# basic-inline-turbidimeter_main_board_v2_.net
KiCad netlist of a schematic drawn in EAGLE
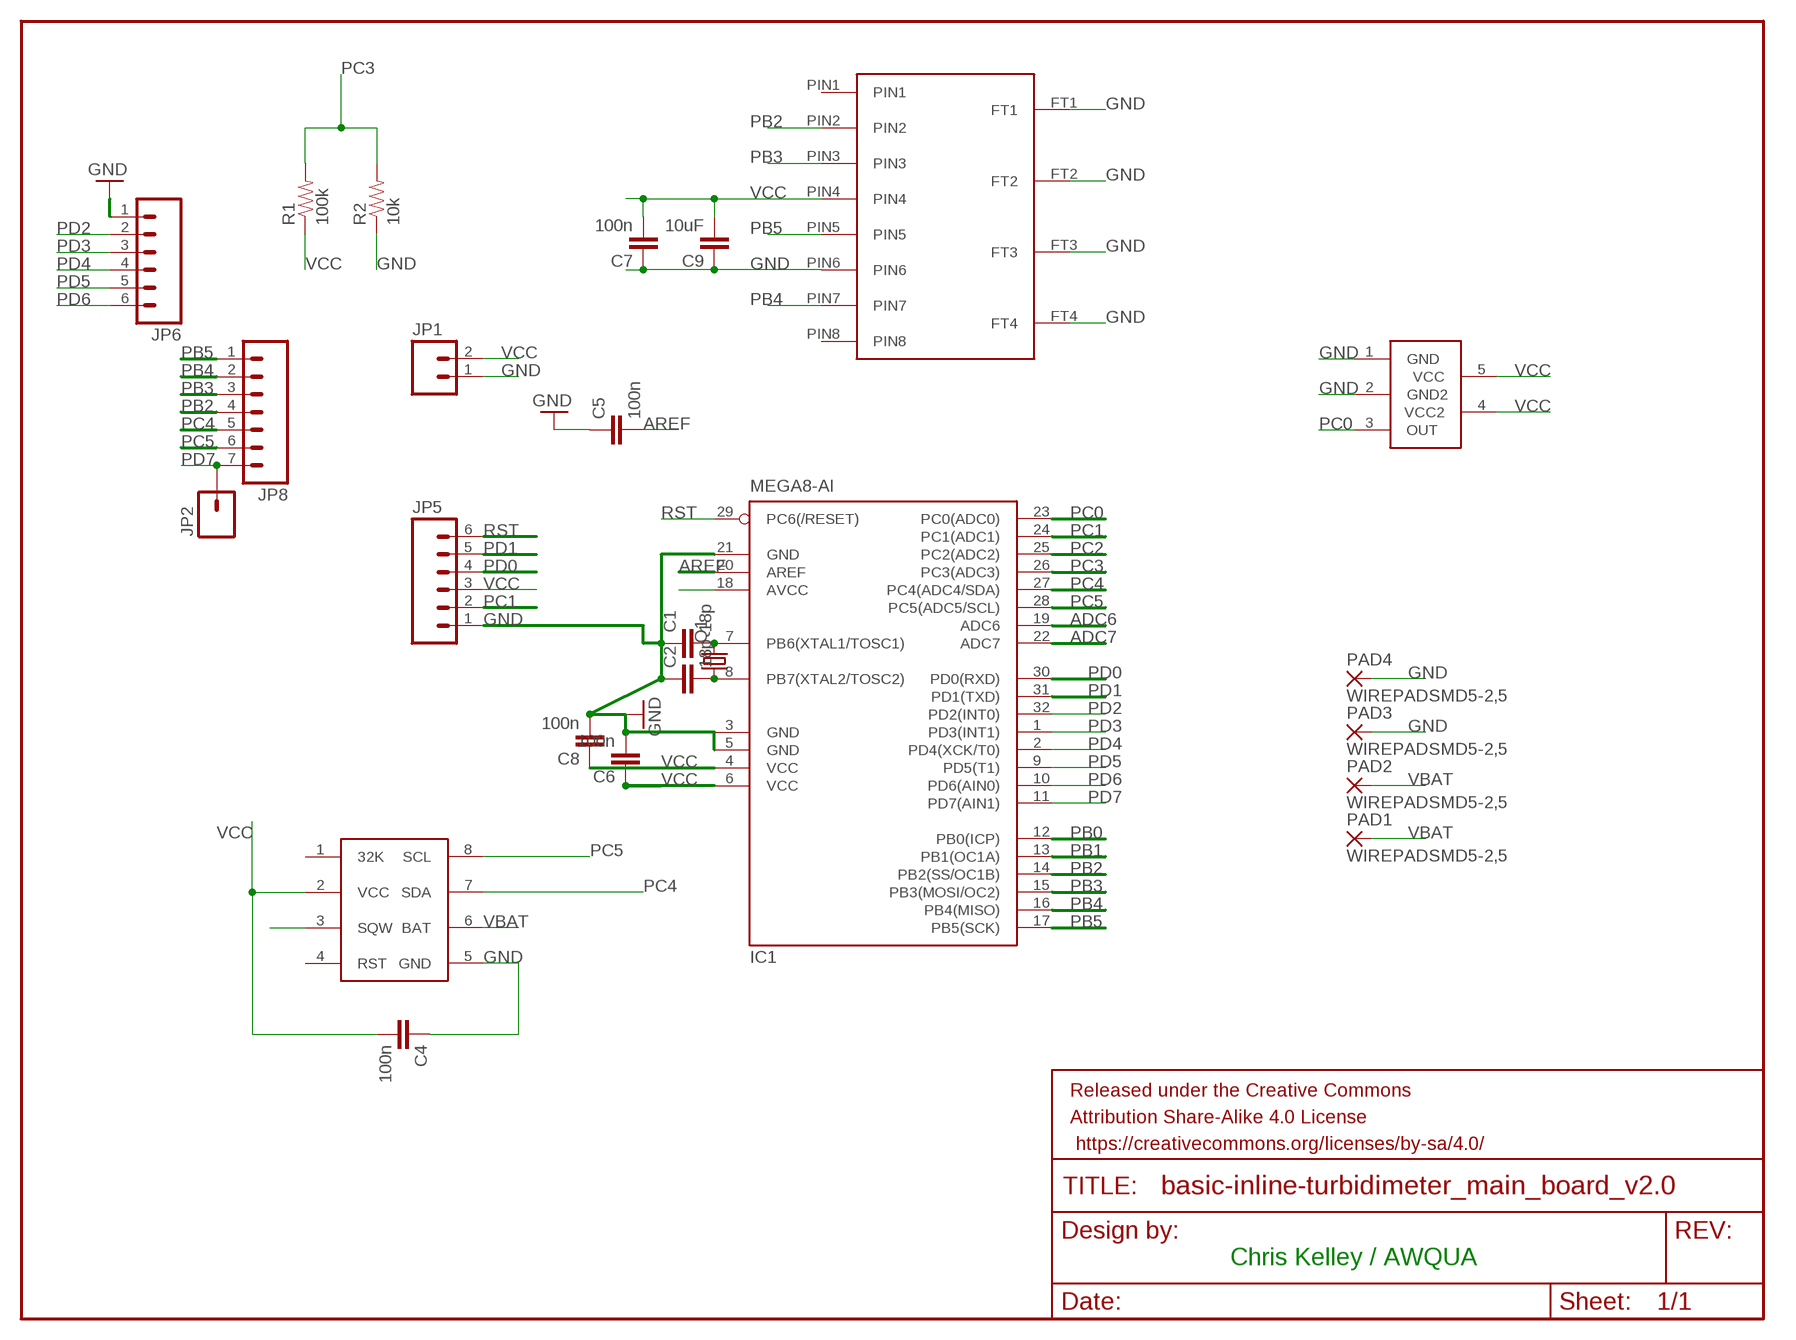
[diagram p0: schematic, sheet 1]

(export (version "E")
  (design (tool "Eeschema 10.0.6"))
  (components
    (comp (ref "*RTC")
      (value "DS3231M")
      (footprint "eagle-import:DS3231M")
      (libsource (lib "eagle-import") (part "DS3231M"))
    )
    (comp (ref "C1")
      (value "18p")
      (footprint "eagle-import:0603-CAP")
      (libsource (lib "eagle-import") (part "CAP0603-CAP"))
    )
    (comp (ref "C2")
      (value "18p")
      (footprint "eagle-import:0603-CAP")
      (libsource (lib "eagle-import") (part "CAP0603-CAP"))
    )
    (comp (ref "C4")
      (value "100n")
      (footprint "eagle-import:0603-CAP")
      (libsource (lib "eagle-import") (part "CAP0603-CAP"))
    )
    (comp (ref "C5")
      (value "100n")
      (footprint "eagle-import:0603-CAP")
      (libsource (lib "eagle-import") (part "CAP0603-CAP"))
    )
    (comp (ref "C6")
      (value "100n")
      (footprint "eagle-import:0603-CAP")
      (libsource (lib "eagle-import") (part "CAP0603-CAP"))
    )
    (comp (ref "C7")
      (value "100n")
      (footprint "eagle-import:0603-CAP")
      (libsource (lib "eagle-import") (part "CAP0603-CAP"))
    )
    (comp (ref "C8")
      (value "100n")
      (footprint "eagle-import:0603-CAP")
      (libsource (lib "eagle-import") (part "CAP0603-CAP"))
    )
    (comp (ref "C9")
      (value "10uF")
      (footprint "eagle-import:0603-CAP")
      (libsource (lib "eagle-import") (part "CAP0603-CAP"))
    )
    (comp (ref "FRAME1")
      (value "FRAME-LETTER")
      (footprint "eagle-import:CREATIVE_COMMONS")
      (libsource (lib "eagle-import") (part "FRAME-LETTER"))
    )
    (comp (ref "IC1")
      (value "MEGA8-AI")
      (footprint "eagle-import:TQFP32-08")
      (fields (field (name "MPN") "ATMEGA8-16AU"))
      (libsource (lib "eagle-import") (part "MEGA8-AI"))
    )
    (comp (ref "JP1")
      (value "M02PTH")
      (footprint "eagle-import:1X02")
      (libsource (lib "eagle-import") (part "M02PTH"))
    )
    (comp (ref "JP2")
      (value "M01PTH")
      (footprint "eagle-import:1X01")
      (libsource (lib "eagle-import") (part "M01PTH"))
    )
    (comp (ref "JP5")
      (value "M06SILK_FEMALE_PTH")
      (footprint "eagle-import:1X06")
      (libsource (lib "eagle-import") (part "M06SILK_FEMALE_PTH"))
    )
    (comp (ref "JP6")
      (value "M06SILK_FEMALE_PTH")
      (footprint "eagle-import:1X06")
      (libsource (lib "eagle-import") (part "M06SILK_FEMALE_PTH"))
    )
    (comp (ref "JP8")
      (value "M07")
      (footprint "eagle-import:1X07")
      (libsource (lib "eagle-import") (part "M07"))
    )
    (comp (ref "MICRO-SD")
      (value "MICROSD-1010030368")
      (footprint "eagle-import:MICROSD-1010030368")
      (libsource (lib "eagle-import") (part "MICROSD-1010030368"))
    )
    (comp (ref "PAD1")
      (value "WIREPADSMD5-2,5")
      (footprint "eagle-import:5-2,5")
      (libsource (lib "eagle-import") (part "WIREPADSMD5-2,5"))
    )
    (comp (ref "PAD2")
      (value "WIREPADSMD5-2,5")
      (footprint "eagle-import:5-2,5")
      (libsource (lib "eagle-import") (part "WIREPADSMD5-2,5"))
    )
    (comp (ref "PAD3")
      (value "WIREPADSMD5-2,5")
      (footprint "eagle-import:5-2,5")
      (libsource (lib "eagle-import") (part "WIREPADSMD5-2,5"))
    )
    (comp (ref "PAD4")
      (value "WIREPADSMD5-2,5")
      (footprint "eagle-import:5-2,5")
      (libsource (lib "eagle-import") (part "WIREPADSMD5-2,5"))
    )
    (comp (ref "Q1")
      (value "CRYSTAL5X3")
      (footprint "eagle-import:CRYSTAL-SMD-5X3")
      (libsource (lib "eagle-import") (part "CRYSTAL5X3"))
    )
    (comp (ref "R1")
      (value "100k")
      (footprint "eagle-import:0603-RES")
      (libsource (lib "eagle-import") (part "RESISTOR0603"))
    )
    (comp (ref "R2")
      (value "10k")
      (footprint "eagle-import:0603-RES")
      (libsource (lib "eagle-import") (part "RESISTOR0603"))
    )
    (comp (ref "T1")
      (value "LMT86")
      (footprint "eagle-import:LMT86")
      (libsource (lib "eagle-import") (part "LMT86"))
    )
  )
  (nets
    (net (code "1") (name "/ADC6") (class "Default")
      (node (ref "IC1") (pin "19") (pinfunction "ADC6_19") (pintype "bidirectional"))
    )
    (net (code "2") (name "/ADC7") (class "Default")
      (node (ref "IC1") (pin "22") (pinfunction "ADC7_22") (pintype "bidirectional"))
    )
    (net (code "3") (name "/AREF") (class "Default")
      (node (ref "C5") (pin "2") (pinfunction "2_2") (pintype "passive"))
      (node (ref "IC1") (pin "20") (pinfunction "AREF_20") (pintype "passive"))
    )
    (net (code "4") (name "/PB0") (class "Default")
      (node (ref "IC1") (pin "12") (pinfunction "PB0(ICP)_12") (pintype "bidirectional"))
    )
    (net (code "5") (name "/PB1") (class "Default")
      (node (ref "IC1") (pin "13") (pinfunction "PB1(OC1A)_13") (pintype "bidirectional"))
    )
    (net (code "6") (name "/PB2") (class "Default")
      (node (ref "IC1") (pin "14") (pinfunction "PB2(SS/OC1B)_14") (pintype "bidirectional"))
      (node (ref "JP8") (pin "4") (pinfunction "4_4") (pintype "passive"))
      (node (ref "MICRO-SD") (pin "PIN2") (pinfunction "PIN2_PIN2") (pintype "bidirectional"))
    )
    (net (code "7") (name "/PB3") (class "Default")
      (node (ref "IC1") (pin "15") (pinfunction "PB3(MOSI/OC2)_15") (pintype "bidirectional"))
      (node (ref "JP8") (pin "3") (pinfunction "3_3") (pintype "passive"))
      (node (ref "MICRO-SD") (pin "PIN3") (pinfunction "PIN3_PIN3") (pintype "bidirectional"))
    )
    (net (code "8") (name "/PB4") (class "Default")
      (node (ref "IC1") (pin "16") (pinfunction "PB4(MISO)_16") (pintype "bidirectional"))
      (node (ref "JP8") (pin "2") (pinfunction "2_2") (pintype "passive"))
      (node (ref "MICRO-SD") (pin "PIN7") (pinfunction "PIN7_PIN7") (pintype "bidirectional"))
    )
    (net (code "9") (name "/PB5") (class "Default")
      (node (ref "IC1") (pin "17") (pinfunction "PB5(SCK)_17") (pintype "bidirectional"))
      (node (ref "JP8") (pin "1") (pinfunction "1_1") (pintype "passive"))
      (node (ref "MICRO-SD") (pin "PIN5") (pinfunction "PIN5_PIN5") (pintype "bidirectional"))
    )
    (net (code "10") (name "/PC0") (class "Default")
      (node (ref "IC1") (pin "23") (pinfunction "PC0(ADC0)_23") (pintype "bidirectional"))
      (node (ref "T1") (pin "3") (pinfunction "OUT_3") (pintype "bidirectional"))
    )
    (net (code "11") (name "/PC1") (class "Default")
      (node (ref "IC1") (pin "24") (pinfunction "PC1(ADC1)_24") (pintype "bidirectional"))
      (node (ref "JP5") (pin "2") (pinfunction "2_2") (pintype "passive"))
    )
    (net (code "12") (name "/PC2") (class "Default")
      (node (ref "IC1") (pin "25") (pinfunction "PC2(ADC2)_25") (pintype "bidirectional"))
    )
    (net (code "13") (name "/PC3") (class "Default")
      (node (ref "IC1") (pin "26") (pinfunction "PC3(ADC3)_26") (pintype "bidirectional"))
      (node (ref "R1") (pin "2") (pinfunction "2_2") (pintype "passive"))
      (node (ref "R2") (pin "2") (pinfunction "2_2") (pintype "passive"))
    )
    (net (code "14") (name "/PC4") (class "Default")
      (node (ref "*RTC") (pin "7") (pinfunction "SDA_7") (pintype "bidirectional"))
      (node (ref "IC1") (pin "27") (pinfunction "PC4(ADC4/SDA)_27") (pintype "bidirectional"))
      (node (ref "JP8") (pin "5") (pinfunction "5_5") (pintype "passive"))
    )
    (net (code "15") (name "/PC5") (class "Default")
      (node (ref "*RTC") (pin "8") (pinfunction "SCL_8") (pintype "bidirectional"))
      (node (ref "IC1") (pin "28") (pinfunction "PC5(ADC5/SCL)_28") (pintype "bidirectional"))
      (node (ref "JP8") (pin "6") (pinfunction "6_6") (pintype "passive"))
    )
    (net (code "16") (name "/PD0") (class "Default")
      (node (ref "IC1") (pin "30") (pinfunction "PD0(RXD)_30") (pintype "bidirectional"))
      (node (ref "JP5") (pin "4") (pinfunction "4_4") (pintype "passive"))
    )
    (net (code "17") (name "/PD1") (class "Default")
      (node (ref "IC1") (pin "31") (pinfunction "PD1(TXD)_31") (pintype "bidirectional"))
      (node (ref "JP5") (pin "5") (pinfunction "5_5") (pintype "passive"))
    )
    (net (code "18") (name "/PD2") (class "Default")
      (node (ref "IC1") (pin "32") (pinfunction "PD2(INT0)_32") (pintype "bidirectional"))
      (node (ref "JP6") (pin "2") (pinfunction "2_2") (pintype "passive"))
    )
    (net (code "19") (name "/PD3") (class "Default")
      (node (ref "IC1") (pin "1") (pinfunction "PD3(INT1)_1") (pintype "bidirectional"))
      (node (ref "JP6") (pin "3") (pinfunction "3_3") (pintype "passive"))
    )
    (net (code "20") (name "/PD4") (class "Default")
      (node (ref "IC1") (pin "2") (pinfunction "PD4(XCK/T0)_2") (pintype "bidirectional"))
      (node (ref "JP6") (pin "4") (pinfunction "4_4") (pintype "passive"))
    )
    (net (code "21") (name "/PD5") (class "Default")
      (node (ref "IC1") (pin "9") (pinfunction "PD5(T1)_9") (pintype "bidirectional"))
      (node (ref "JP6") (pin "5") (pinfunction "5_5") (pintype "passive"))
    )
    (net (code "22") (name "/PD6") (class "Default")
      (node (ref "IC1") (pin "10") (pinfunction "PD6(AIN0)_10") (pintype "bidirectional"))
      (node (ref "JP6") (pin "6") (pinfunction "6_6") (pintype "passive"))
    )
    (net (code "23") (name "/PD7") (class "Default")
      (node (ref "IC1") (pin "11") (pinfunction "PD7(AIN1)_11") (pintype "bidirectional"))
      (node (ref "JP2") (pin "1") (pinfunction "1_1") (pintype "passive"))
      (node (ref "JP8") (pin "7") (pinfunction "7_7") (pintype "passive"))
    )
    (net (code "24") (name "/RST") (class "Default")
      (node (ref "IC1") (pin "29") (pinfunction "PC6(/RESET)_29") (pintype "bidirectional"))
      (node (ref "JP5") (pin "6") (pinfunction "6_6") (pintype "passive"))
    )
    (net (code "25") (name "/VBAT") (class "Default")
      (node (ref "*RTC") (pin "6") (pinfunction "BAT_6") (pintype "bidirectional"))
      (node (ref "PAD1") (pin "1") (pinfunction "P_1") (pintype "passive"))
      (node (ref "PAD2") (pin "1") (pinfunction "P_1") (pintype "passive"))
    )
    (net (code "26") (name "/VCC") (class "Default")
      (node (ref "*RTC") (pin "2") (pinfunction "VCC_2") (pintype "bidirectional"))
      (node (ref "C4") (pin "2") (pinfunction "2_2") (pintype "passive"))
      (node (ref "C6") (pin "1") (pinfunction "1_1") (pintype "passive"))
      (node (ref "C7") (pin "2") (pinfunction "2_2") (pintype "passive"))
      (node (ref "C8") (pin "1") (pinfunction "1_1") (pintype "passive"))
      (node (ref "C9") (pin "2") (pinfunction "2_2") (pintype "passive"))
      (node (ref "IC1") (pin "18") (pinfunction "AVCC_18") (pintype "power_in"))
      (node (ref "IC1") (pin "4") (pinfunction "VCC_4") (pintype "power_in"))
      (node (ref "IC1") (pin "6") (pinfunction "VCC_6") (pintype "power_in"))
      (node (ref "JP1") (pin "2") (pinfunction "2_2") (pintype "passive"))
      (node (ref "JP5") (pin "3") (pinfunction "3_3") (pintype "passive"))
      (node (ref "MICRO-SD") (pin "PIN4") (pinfunction "PIN4_PIN4") (pintype "bidirectional"))
      (node (ref "R1") (pin "1") (pinfunction "1_1") (pintype "passive"))
      (node (ref "T1") (pin "4") (pinfunction "VCC2_4") (pintype "bidirectional"))
      (node (ref "T1") (pin "5") (pinfunction "VCC_5") (pintype "bidirectional"))
    )
    (net (code "27") (name "GND") (class "Default")
      (node (ref "*RTC") (pin "5") (pinfunction "GND_5") (pintype "bidirectional"))
      (node (ref "C1") (pin "1") (pinfunction "1_1") (pintype "passive"))
      (node (ref "C2") (pin "1") (pinfunction "1_1") (pintype "passive"))
      (node (ref "C4") (pin "1") (pinfunction "1_1") (pintype "passive"))
      (node (ref "C5") (pin "1") (pinfunction "1_1") (pintype "passive"))
      (node (ref "C6") (pin "2") (pinfunction "2_2") (pintype "passive"))
      (node (ref "C7") (pin "1") (pinfunction "1_1") (pintype "passive"))
      (node (ref "C8") (pin "2") (pinfunction "2_2") (pintype "passive"))
      (node (ref "C9") (pin "1") (pinfunction "1_1") (pintype "passive"))
      (node (ref "IC1") (pin "21") (pinfunction "GND_21") (pintype "power_in"))
      (node (ref "IC1") (pin "3") (pinfunction "GND_3") (pintype "power_in"))
      (node (ref "IC1") (pin "5") (pinfunction "GND_5") (pintype "power_in"))
      (node (ref "JP1") (pin "1") (pinfunction "1_1") (pintype "passive"))
      (node (ref "JP5") (pin "1") (pinfunction "1_1") (pintype "passive"))
      (node (ref "JP6") (pin "1") (pinfunction "1_1") (pintype "passive"))
      (node (ref "MICRO-SD") (pin "FT1") (pinfunction "FT1_FT1") (pintype "bidirectional"))
      (node (ref "MICRO-SD") (pin "FT2") (pinfunction "FT2_FT2") (pintype "bidirectional"))
      (node (ref "MICRO-SD") (pin "FT3") (pinfunction "FT3_FT3") (pintype "bidirectional"))
      (node (ref "MICRO-SD") (pin "FT4") (pinfunction "FT4_FT4") (pintype "bidirectional"))
      (node (ref "MICRO-SD") (pin "PIN6") (pinfunction "PIN6_PIN6") (pintype "bidirectional"))
      (node (ref "PAD3") (pin "1") (pinfunction "P_1") (pintype "passive"))
      (node (ref "PAD4") (pin "1") (pinfunction "P_1") (pintype "passive"))
      (node (ref "R2") (pin "1") (pinfunction "1_1") (pintype "passive"))
      (node (ref "T1") (pin "1") (pinfunction "GND_1") (pintype "bidirectional"))
      (node (ref "T1") (pin "2") (pinfunction "GND2_2") (pintype "bidirectional"))
    )
    (net (code "28") (name "Net-(IC1-PB6(XTAL1{slash}TOSC1))") (class "Default")
      (node (ref "C1") (pin "2") (pinfunction "2_2") (pintype "passive"))
      (node (ref "IC1") (pin "7") (pinfunction "PB6(XTAL1/TOSC1)_7") (pintype "bidirectional"))
      (node (ref "Q1") (pin "3") (pinfunction "2_3") (pintype "passive"))
    )
    (net (code "29") (name "Net-(IC1-PB7(XTAL2{slash}TOSC2))") (class "Default")
      (node (ref "C2") (pin "2") (pinfunction "2_2") (pintype "passive"))
      (node (ref "IC1") (pin "8") (pinfunction "PB7(XTAL2/TOSC2)_8") (pintype "bidirectional"))
      (node (ref "Q1") (pin "1") (pinfunction "1_1") (pintype "passive"))
    )
    (net (code "30") (name "unconnected-(*RTC-32K-Pad1)") (class "Default")
      (node (ref "*RTC") (pin "1") (pinfunction "32K_1") (pintype "bidirectional"))
    )
    (net (code "31") (name "unconnected-(*RTC-RST-Pad4)") (class "Default")
      (node (ref "*RTC") (pin "4") (pinfunction "RST_4") (pintype "bidirectional"))
    )
    (net (code "32") (name "unconnected-(*RTC-SQW-Pad3)") (class "Default")
      (node (ref "*RTC") (pin "3") (pinfunction "SQW_3") (pintype "bidirectional"))
    )
    (net (code "33") (name "unconnected-(MICRO-SD-PadPIN1)") (class "Default")
      (node (ref "MICRO-SD") (pin "PIN1") (pinfunction "PIN1_PIN1") (pintype "bidirectional"))
    )
    (net (code "34") (name "unconnected-(MICRO-SD-PadPIN8)") (class "Default")
      (node (ref "MICRO-SD") (pin "PIN8") (pinfunction "PIN8_PIN8") (pintype "bidirectional"))
    )
  )
)
